# PARK-BRAKE.net
KiCad netlist of a schematic drawn in Altium Designer
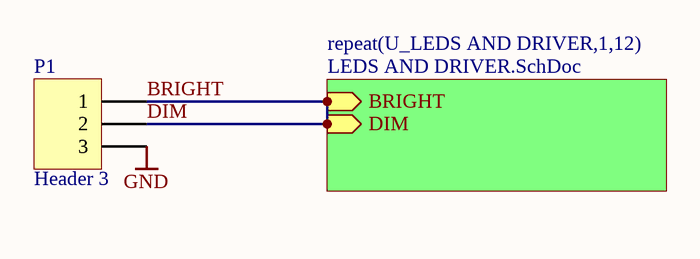
[diagram p0: PARK-BRAKE.SchDoc]

(export (version "E")
  (design (tool "Eeschema 10.0.6"))
  (components
    (comp (ref "P1")
      (value "Header 3")
      (footprint "TAIL")
      (description "Header, 3-Pin")
      (fields (field (name "PUBLISHER") "Altium Limited"))
      (libsource (lib "Miscellaneous Connectors") (part "Header 3"))
    )
  )
  (nets
    (net (code "1") (name "/BRIGHT") (class "Default")
      (node (ref "P1") (pin "1") (pinfunction "1_1") (pintype "passive"))
      (node (ref "P1") (pin "2") (pinfunction "2_2") (pintype "passive"))
    )
    (net (code "2") (name "GND") (class "Default")
      (node (ref "P1") (pin "3") (pinfunction "3_3") (pintype "passive"))
    )
  )
)
